# Adafruit_SHT45.net
KiCad netlist of a schematic drawn in EAGLE
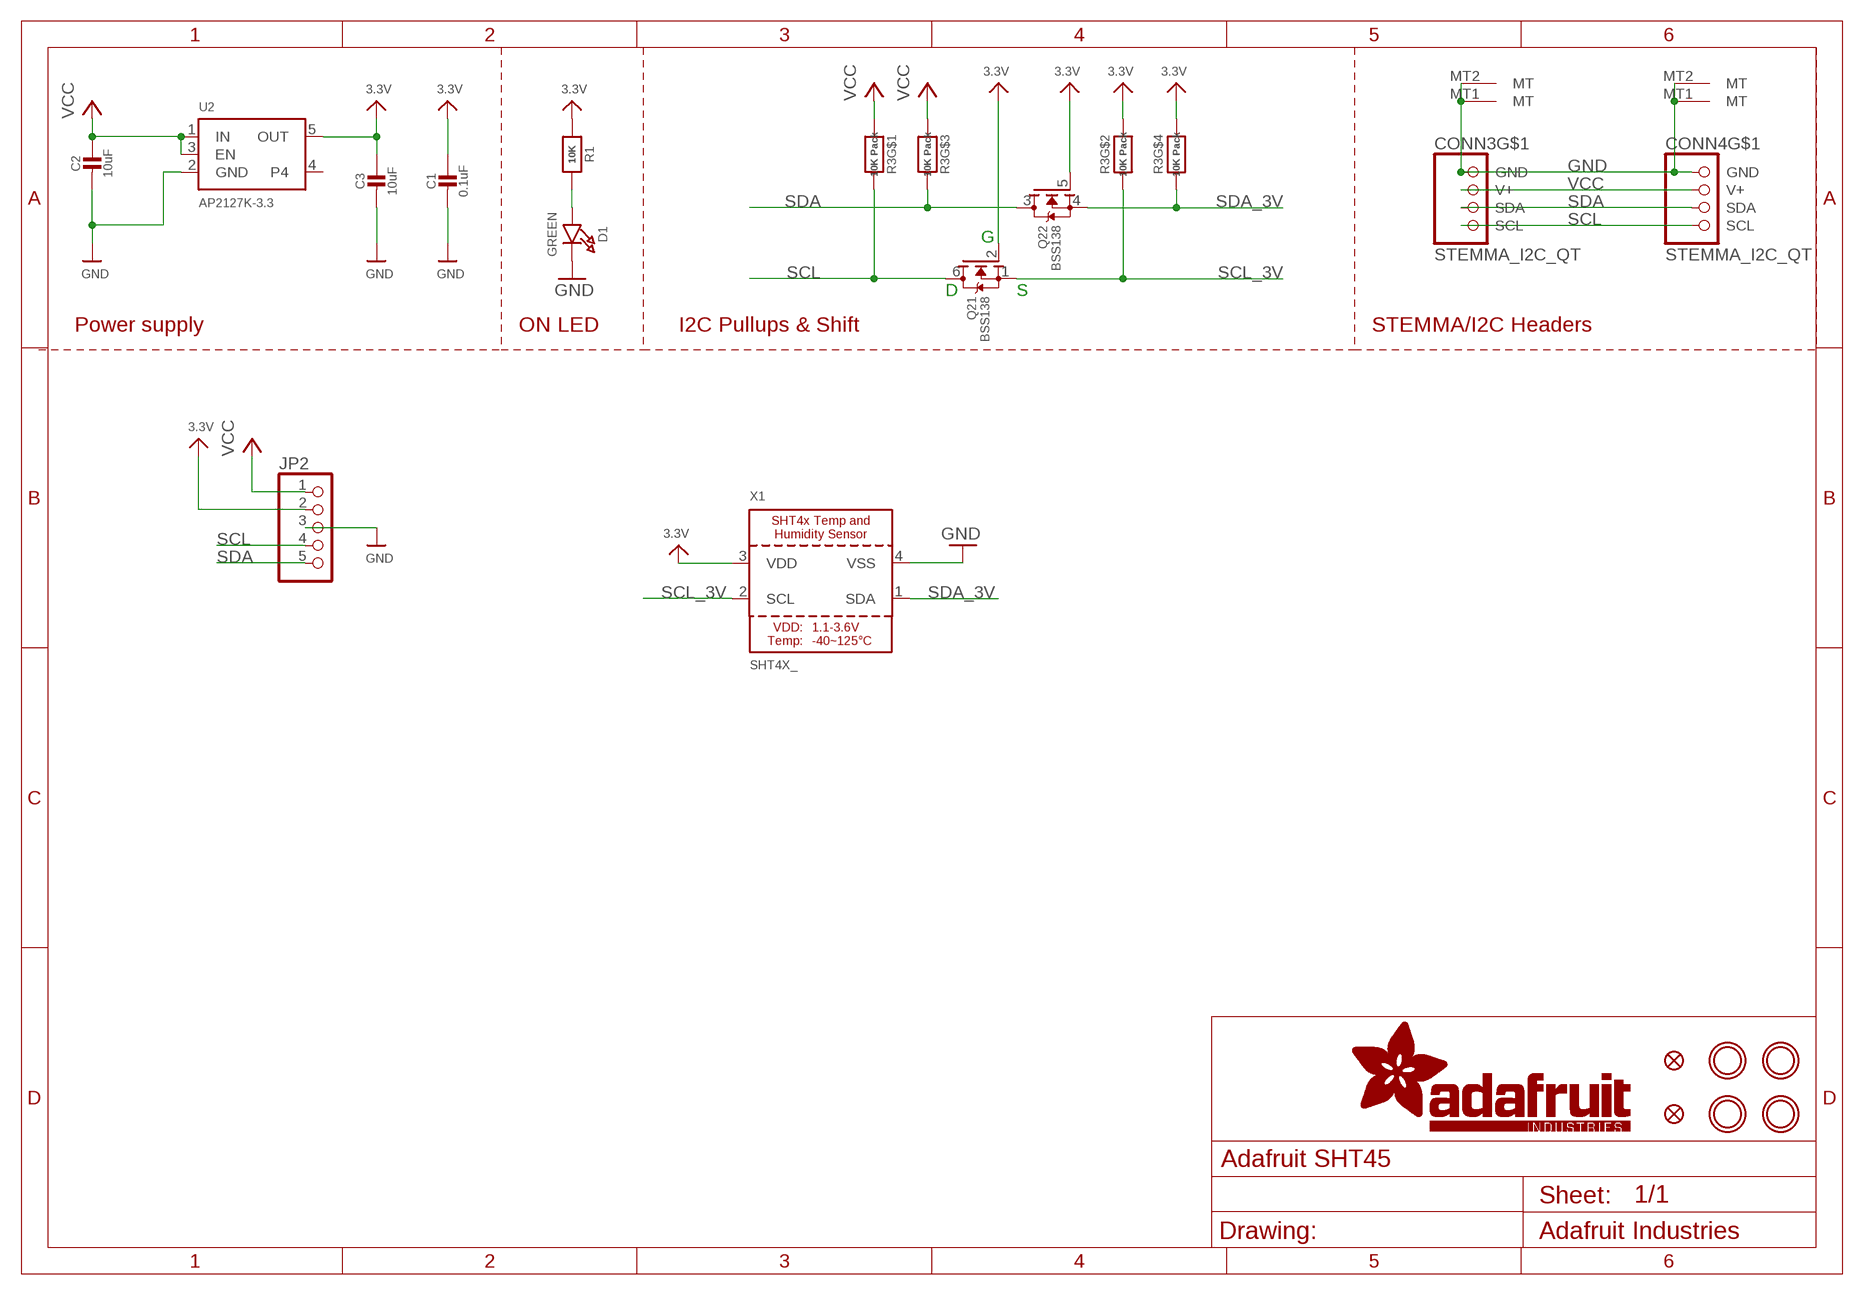
[diagram p0: schematic, sheet 1]

(export (version "E")
  (design (tool "Eeschema 10.0.6"))
  (components
    (comp (ref "C1")
      (value "0.1uF")
      (footprint "eagle-import:0603-NO")
      (libsource (lib "eagle-import") (part "CAP_CERAMIC0603_NO"))
    )
    (comp (ref "C2")
      (value "10uF")
      (footprint "eagle-import:0805-NO")
      (libsource (lib "eagle-import") (part "CAP_CERAMIC0805-NOOUTLINE"))
    )
    (comp (ref "C3")
      (value "10uF")
      (footprint "eagle-import:0805-NO")
      (libsource (lib "eagle-import") (part "CAP_CERAMIC0805-NOOUTLINE"))
    )
    (comp (ref "CONN3")
      (value "STEMMA_I2C_QT")
      (footprint "eagle-import:JST_SH4")
      (libsource (lib "eagle-import") (part "STEMMA_I2C_QT"))
    )
    (comp (ref "CONN4")
      (value "STEMMA_I2C_QT")
      (footprint "eagle-import:JST_SH4")
      (libsource (lib "eagle-import") (part "STEMMA_I2C_QT"))
    )
    (comp (ref "D1")
      (value "GREEN")
      (footprint "eagle-import:CHIPLED_0603_NOOUTLINE")
      (libsource (lib "eagle-import") (part "LED0603_NOOUTLINE"))
    )
    (comp (ref "FID3")
      (value "FIDUCIAL_1MM")
      (footprint "eagle-import:FIDUCIAL_1MM")
      (libsource (lib "eagle-import") (part "FIDUCIAL_1MM"))
    )
    (comp (ref "FID4")
      (value "FIDUCIAL_1MM")
      (footprint "eagle-import:FIDUCIAL_1MM")
      (libsource (lib "eagle-import") (part "FIDUCIAL_1MM"))
    )
    (comp (ref "JP2")
      (value "HEADER-1X570MIL")
      (footprint "eagle-import:1X05_ROUND_70")
      (libsource (lib "eagle-import") (part "HEADER-1X570MIL"))
    )
    (comp (ref "Q2")
      (value "BSS138")
      (footprint "eagle-import:SOT363")
      (libsource (lib "eagle-import") (part "MOSFET-N_DUAL"))
    )
    (comp (ref "R1")
      (value "10K")
      (footprint "eagle-import:0603-NO")
      (libsource (lib "eagle-import") (part "RESISTOR_0603_NOOUT"))
    )
    (comp (ref "R3")
      (value "10K Pack")
      (footprint "eagle-import:RESPACK_4X0603")
      (libsource (lib "eagle-import") (part "RESISTOR_4PACK"))
    )
    (comp (ref "U$1")
      (value "MOUNTINGHOLE2.5")
      (footprint "eagle-import:MOUNTINGHOLE_2.5_PLATED")
      (libsource (lib "eagle-import") (part "MOUNTINGHOLE2.5"))
    )
    (comp (ref "U$17")
      (value "MOUNTINGHOLE2.5")
      (footprint "eagle-import:MOUNTINGHOLE_2.5_PLATED")
      (libsource (lib "eagle-import") (part "MOUNTINGHOLE2.5"))
    )
    (comp (ref "U$19")
      (value "MOUNTINGHOLE2.5")
      (footprint "eagle-import:MOUNTINGHOLE_2.5_PLATED")
      (libsource (lib "eagle-import") (part "MOUNTINGHOLE2.5"))
    )
    (comp (ref "U$21")
      (value "MOUNTINGHOLE2.5")
      (footprint "eagle-import:MOUNTINGHOLE_2.5_PLATED")
      (libsource (lib "eagle-import") (part "MOUNTINGHOLE2.5"))
    )
    (comp (ref "U2")
      (value "AP2127K-3.3")
      (footprint "eagle-import:SOT23-5")
      (libsource (lib "eagle-import") (part "VREG_SOT23-5"))
    )
    (comp (ref "X1")
      (value "SHT4X_")
      (footprint "eagle-import:SHT4X")
      (libsource (lib "eagle-import") (part "SHT4X_"))
    )
  )
  (nets
    (net (code "1") (name "/SCL") (class "Default")
      (node (ref "CONN3") (pin "4") (pinfunction "SCL_4") (pintype "passive"))
      (node (ref "CONN4") (pin "4") (pinfunction "SCL_4") (pintype "passive"))
      (node (ref "JP2") (pin "4") (pinfunction "4_4") (pintype "passive"))
      (node (ref "Q2") (pin "6") (pinfunction "D_6") (pintype "bidirectional"))
      (node (ref "R3") (pin "8") (pinfunction "2_8") (pintype "passive"))
    )
    (net (code "2") (name "/SCL_3V") (class "Default")
      (node (ref "Q2") (pin "1") (pinfunction "S_1") (pintype "bidirectional"))
      (node (ref "R3") (pin "7") (pinfunction "2_7") (pintype "passive"))
      (node (ref "X1") (pin "2") (pinfunction "SCL_2") (pintype "bidirectional"))
    )
    (net (code "3") (name "/SDA") (class "Default")
      (node (ref "CONN3") (pin "3") (pinfunction "SDA_3") (pintype "passive"))
      (node (ref "CONN4") (pin "3") (pinfunction "SDA_3") (pintype "passive"))
      (node (ref "JP2") (pin "5") (pinfunction "5_5") (pintype "passive"))
      (node (ref "Q2") (pin "3") (pinfunction "D_3") (pintype "bidirectional"))
      (node (ref "R3") (pin "6") (pinfunction "2_6") (pintype "passive"))
    )
    (net (code "4") (name "/SDA_3V") (class "Default")
      (node (ref "Q2") (pin "4") (pinfunction "S_4") (pintype "bidirectional"))
      (node (ref "R3") (pin "5") (pinfunction "2_5") (pintype "passive"))
      (node (ref "X1") (pin "1") (pinfunction "SDA_1") (pintype "bidirectional"))
    )
    (net (code "5") (name "3.3V") (class "Default")
      (node (ref "C1") (pin "1") (pinfunction "1_1") (pintype "passive"))
      (node (ref "C3") (pin "1") (pinfunction "1_1") (pintype "passive"))
      (node (ref "JP2") (pin "2") (pinfunction "2_2") (pintype "passive"))
      (node (ref "Q2") (pin "2") (pinfunction "G_2") (pintype "bidirectional"))
      (node (ref "Q2") (pin "5") (pinfunction "G_5") (pintype "bidirectional"))
      (node (ref "R1") (pin "1") (pinfunction "1_1") (pintype "passive"))
      (node (ref "R3") (pin "2") (pinfunction "1_2") (pintype "passive"))
      (node (ref "R3") (pin "4") (pinfunction "1_4") (pintype "passive"))
      (node (ref "U2") (pin "5") (pinfunction "OUT_5") (pintype "power_in"))
      (node (ref "X1") (pin "3") (pinfunction "VDD_3") (pintype "power_in"))
    )
    (net (code "6") (name "GND") (class "Default")
      (node (ref "C1") (pin "2") (pinfunction "2_2") (pintype "passive"))
      (node (ref "C2") (pin "2") (pinfunction "2_2") (pintype "passive"))
      (node (ref "C3") (pin "2") (pinfunction "2_2") (pintype "passive"))
      (node (ref "CONN3") (pin "1") (pinfunction "GND_1") (pintype "passive"))
      (node (ref "CONN3") (pin "MT1") (pinfunction "MT_MT1") (pintype "bidirectional"))
      (node (ref "CONN3") (pin "MT2") (pinfunction "MT_MT2") (pintype "bidirectional"))
      (node (ref "CONN4") (pin "1") (pinfunction "GND_1") (pintype "passive"))
      (node (ref "CONN4") (pin "MT1") (pinfunction "MT_MT1") (pintype "bidirectional"))
      (node (ref "CONN4") (pin "MT2") (pinfunction "MT_MT2") (pintype "bidirectional"))
      (node (ref "D1") (pin "C") (pinfunction "C_C") (pintype "passive"))
      (node (ref "JP2") (pin "3") (pinfunction "3_3") (pintype "passive"))
      (node (ref "U2") (pin "2") (pinfunction "GND_2") (pintype "power_in"))
      (node (ref "X1") (pin "4") (pinfunction "VSS_4") (pintype "power_in"))
    )
    (net (code "7") (name "Net-(D1-PadA)") (class "Default")
      (node (ref "D1") (pin "A") (pinfunction "A_A") (pintype "passive"))
      (node (ref "R1") (pin "2") (pinfunction "2_2") (pintype "passive"))
    )
    (net (code "8") (name "VCC") (class "Default")
      (node (ref "C2") (pin "1") (pinfunction "1_1") (pintype "passive"))
      (node (ref "CONN3") (pin "2") (pinfunction "V+_2") (pintype "passive"))
      (node (ref "CONN4") (pin "2") (pinfunction "V+_2") (pintype "passive"))
      (node (ref "JP2") (pin "1") (pinfunction "1_1") (pintype "passive"))
      (node (ref "R3") (pin "1") (pinfunction "1_1") (pintype "passive"))
      (node (ref "R3") (pin "3") (pinfunction "1_3") (pintype "passive"))
      (node (ref "U2") (pin "1") (pinfunction "IN_1") (pintype "power_in"))
      (node (ref "U2") (pin "3") (pinfunction "EN_3") (pintype "input"))
    )
    (net (code "9") (name "unconnected-(U2-P4-Pad4)") (class "Default")
      (node (ref "U2") (pin "4") (pinfunction "P4_4") (pintype "bidirectional"))
    )
  )
)
